# pqar-wirebonded-rev1.net
KiCad netlist of a schematic drawn in EAGLE
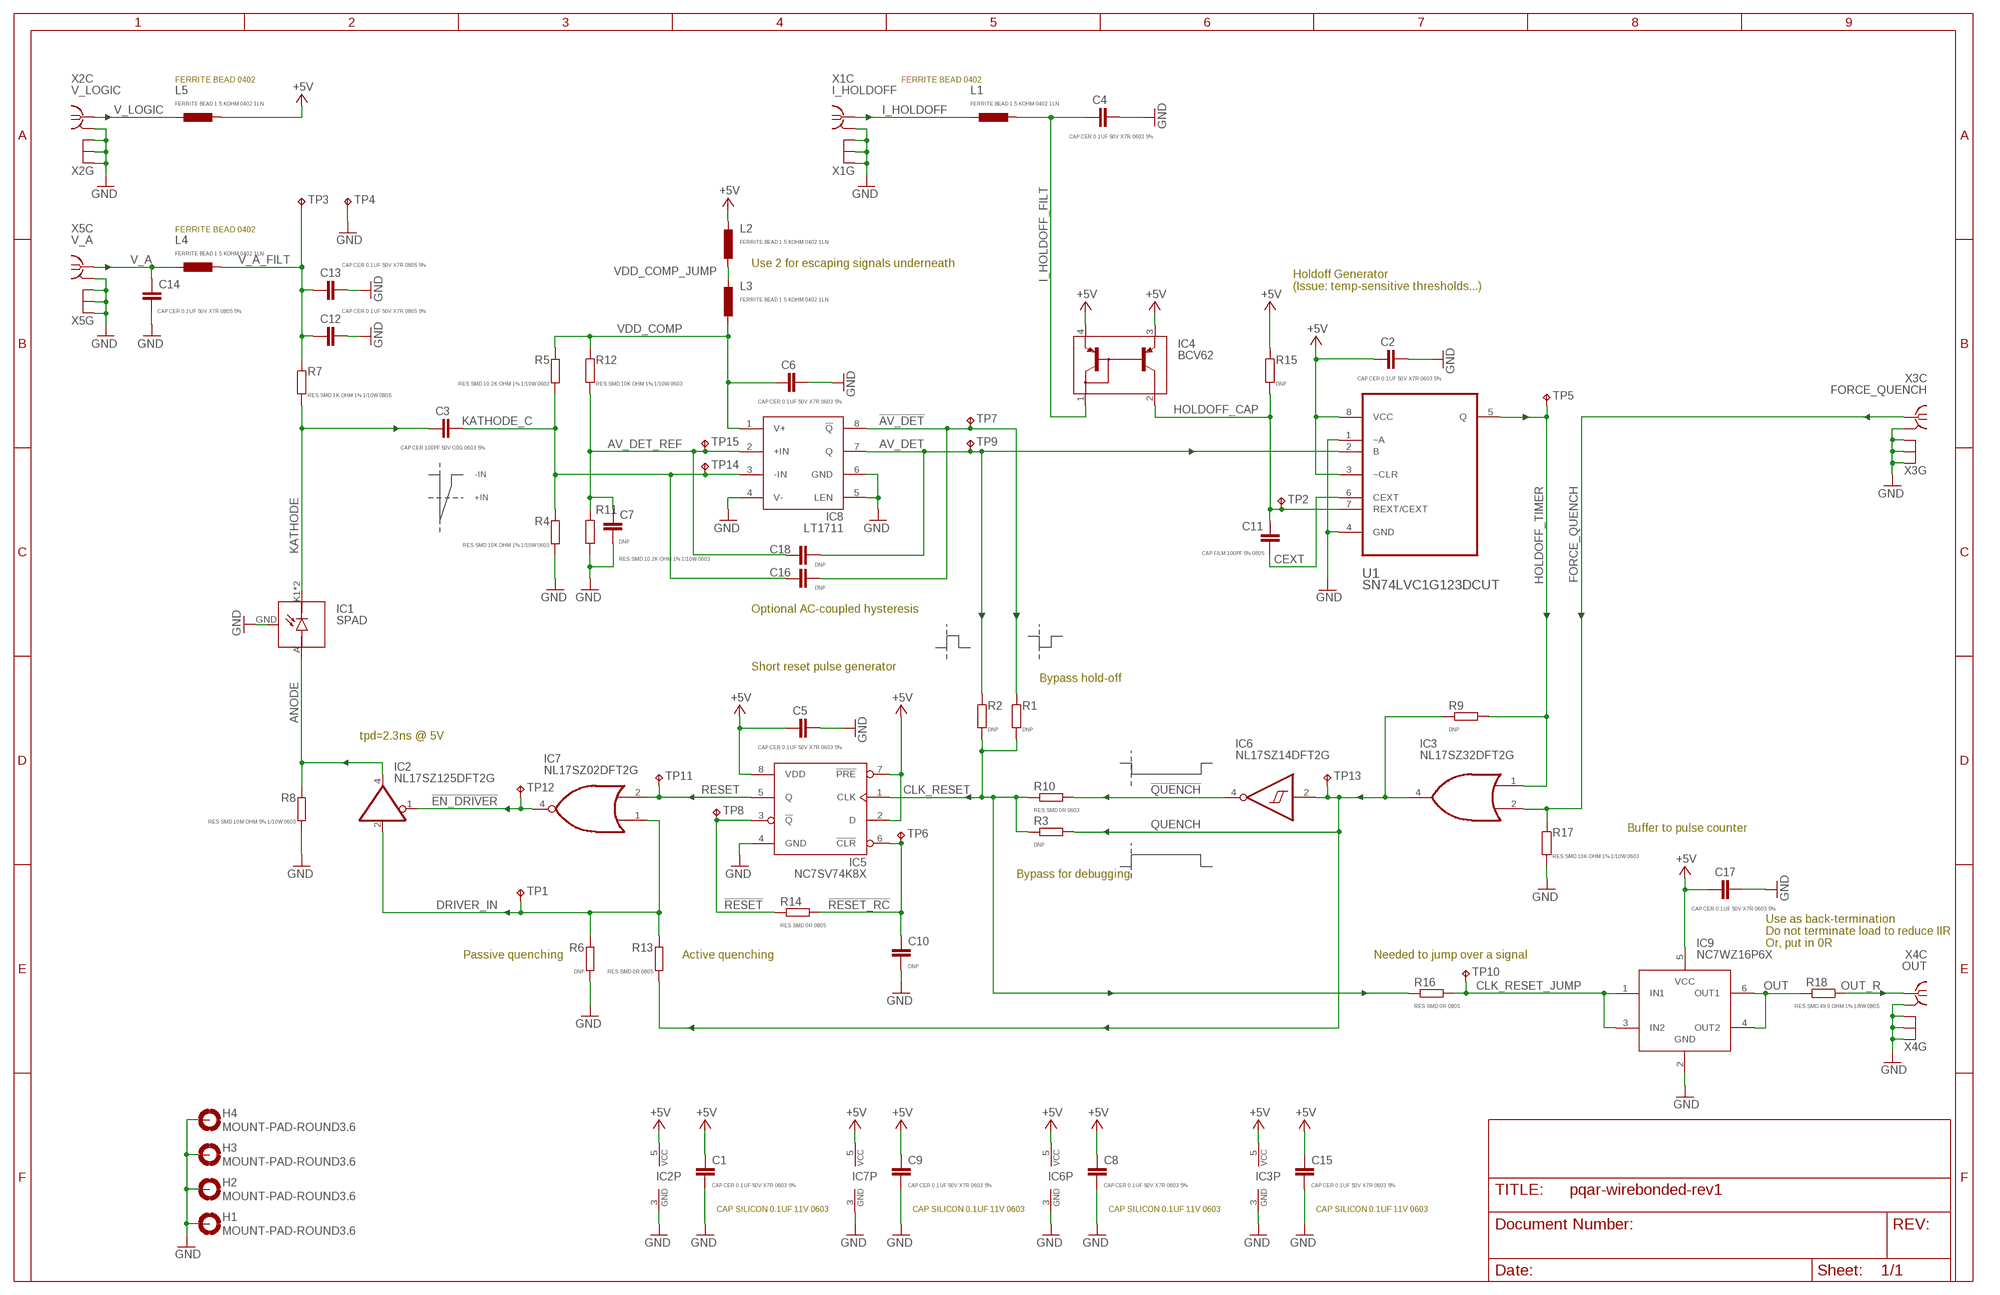
[diagram p0: schematic, sheet 1]

(export (version "E")
  (design (tool "Eeschema 10.0.6"))
  (components
    (comp (ref "C1")
      (value "CAP CER 0.1UF 50V X7R 0603 5%")
      (footprint "eagle-import:C0603")
      (libsource (lib "eagle-import") (part "C-EUC0603"))
    )
    (comp (ref "C2")
      (value "CAP CER 0.1UF 50V X7R 0603 5%")
      (footprint "eagle-import:C0603")
      (libsource (lib "eagle-import") (part "C-EUC0603"))
    )
    (comp (ref "C3")
      (value "CAP CER 100PF 50V C0G 0603 5%")
      (footprint "eagle-import:C0603")
      (libsource (lib "eagle-import") (part "C-EUC0603"))
    )
    (comp (ref "C4")
      (value "CAP CER 0.1UF 50V X7R 0603 5%")
      (footprint "eagle-import:C0603")
      (libsource (lib "eagle-import") (part "C-EUC0603"))
    )
    (comp (ref "C5")
      (value "CAP CER 0.1UF 50V X7R 0603 5%")
      (footprint "eagle-import:C0603")
      (libsource (lib "eagle-import") (part "C-EUC0603"))
    )
    (comp (ref "C6")
      (value "CAP CER 0.1UF 50V X7R 0603 5%")
      (footprint "eagle-import:C0603")
      (libsource (lib "eagle-import") (part "C-EUC0603"))
    )
    (comp (ref "C7")
      (value "DNP")
      (footprint "eagle-import:C0603")
      (libsource (lib "eagle-import") (part "C-EUC0603"))
    )
    (comp (ref "C8")
      (value "CAP CER 0.1UF 50V X7R 0603 5%")
      (footprint "eagle-import:C0603")
      (libsource (lib "eagle-import") (part "C-EUC0603"))
    )
    (comp (ref "C9")
      (value "CAP CER 0.1UF 50V X7R 0603 5%")
      (footprint "eagle-import:C0603")
      (libsource (lib "eagle-import") (part "C-EUC0603"))
    )
    (comp (ref "C10")
      (value "DNP")
      (footprint "eagle-import:C0805")
      (libsource (lib "eagle-import") (part "C-EUC0805"))
    )
    (comp (ref "C11")
      (value "CAP FILM 100PF 5% 0805")
      (footprint "eagle-import:C0805")
      (libsource (lib "eagle-import") (part "C-EUC0805"))
    )
    (comp (ref "C12")
      (value "CAP CER 0.1UF 50V X7R 0805 5%")
      (footprint "eagle-import:C0805")
      (libsource (lib "eagle-import") (part "C-EUC0805"))
    )
    (comp (ref "C13")
      (value "CAP CER 0.1UF 50V X7R 0805 5%")
      (footprint "eagle-import:C0805")
      (libsource (lib "eagle-import") (part "C-EUC0805"))
    )
    (comp (ref "C14")
      (value "CAP CER 0.1UF 50V X7R 0805 5%")
      (footprint "eagle-import:C0805")
      (libsource (lib "eagle-import") (part "C-EUC0805"))
    )
    (comp (ref "C15")
      (value "CAP CER 0.1UF 50V X7R 0603 5%")
      (footprint "eagle-import:C0603")
      (libsource (lib "eagle-import") (part "C-EUC0603"))
    )
    (comp (ref "C16")
      (value "DNP")
      (footprint "eagle-import:C0805")
      (libsource (lib "eagle-import") (part "C-EUC0805"))
    )
    (comp (ref "C17")
      (value "CAP CER 0.1UF 50V X7R 0603 5%")
      (footprint "eagle-import:C0603")
      (libsource (lib "eagle-import") (part "C-EUC0603"))
    )
    (comp (ref "C18")
      (value "DNP")
      (footprint "eagle-import:C0805")
      (libsource (lib "eagle-import") (part "C-EUC0805"))
    )
    (comp (ref "H1")
      (value "MOUNT-PAD-ROUND3.6")
      (footprint "eagle-import:3,6-PAD")
      (libsource (lib "eagle-import") (part "MOUNT-PAD-ROUND3.6"))
    )
    (comp (ref "H2")
      (value "MOUNT-PAD-ROUND3.6")
      (footprint "eagle-import:3,6-PAD")
      (libsource (lib "eagle-import") (part "MOUNT-PAD-ROUND3.6"))
    )
    (comp (ref "H3")
      (value "MOUNT-PAD-ROUND3.6")
      (footprint "eagle-import:3,6-PAD")
      (libsource (lib "eagle-import") (part "MOUNT-PAD-ROUND3.6"))
    )
    (comp (ref "H4")
      (value "MOUNT-PAD-ROUND3.6")
      (footprint "eagle-import:3,6-PAD")
      (libsource (lib "eagle-import") (part "MOUNT-PAD-ROUND3.6"))
    )
    (comp (ref "IC1")
      (value "SPAD")
      (footprint "eagle-import:SPAD-WIREBOND-GENERIC-CRYO")
      (libsource (lib "eagle-import") (part "SPAD-GENERIC"))
    )
    (comp (ref "IC2")
      (value "NL17SZ125DFT2G")
      (footprint "eagle-import:SC70-5")
      (libsource (lib "eagle-import") (part "741G125DCKAHC"))
    )
    (comp (ref "IC3")
      (value "NL17SZ32DFT2G")
      (footprint "eagle-import:SC70-5")
      (libsource (lib "eagle-import") (part "741G32DCKAUC"))
    )
    (comp (ref "IC4")
      (value "BCV62")
      (footprint "eagle-import:SOT143B")
      (libsource (lib "eagle-import") (part "BCV62"))
    )
    (comp (ref "IC5")
      (value "NC7SV74K8X")
      (footprint "eagle-import:US8_3.1MM_JDEC_MO-187")
      (libsource (lib "eagle-import") (part "NC7SV74K8X"))
    )
    (comp (ref "IC6")
      (value "NL17SZ14DFT2G")
      (footprint "eagle-import:SC70-5")
      (libsource (lib "eagle-import") (part "741G14DCKAHC"))
    )
    (comp (ref "IC7")
      (value "NL17SZ02DFT2G")
      (footprint "eagle-import:SC70-5")
      (libsource (lib "eagle-import") (part "741G02DCKLVC"))
    )
    (comp (ref "IC8")
      (value "LT1711")
      (footprint "eagle-import:MSOP8")
      (libsource (lib "eagle-import") (part "LTC1711"))
    )
    (comp (ref "IC9")
      (value "NC7WZ16P6X")
      (footprint "eagle-import:SC70-6L")
      (libsource (lib "eagle-import") (part "NC7WZ16P6X"))
    )
    (comp (ref "L1")
      (value "FERRITE BEAD 1.5 KOHM 0402 1LN")
      (footprint "eagle-import:R0402")
      (libsource (lib "eagle-import") (part "INDUCTOR0402"))
    )
    (comp (ref "L2")
      (value "FERRITE BEAD 1.5 KOHM 0402 1LN")
      (footprint "eagle-import:R0402")
      (libsource (lib "eagle-import") (part "INDUCTOR0402"))
    )
    (comp (ref "L3")
      (value "FERRITE BEAD 1.5 KOHM 0402 1LN")
      (footprint "eagle-import:R0402")
      (libsource (lib "eagle-import") (part "INDUCTOR0402"))
    )
    (comp (ref "L4")
      (value "FERRITE BEAD 1.5 KOHM 0402 1LN")
      (footprint "eagle-import:R0402")
      (libsource (lib "eagle-import") (part "INDUCTOR0402"))
    )
    (comp (ref "L5")
      (value "FERRITE BEAD 1.5 KOHM 0402 1LN")
      (footprint "eagle-import:R0402")
      (libsource (lib "eagle-import") (part "INDUCTOR0402"))
    )
    (comp (ref "R1")
      (value "DNP")
      (footprint "eagle-import:R0805")
      (libsource (lib "eagle-import") (part "rcl-modified-footprints_R-EU_R0805"))
    )
    (comp (ref "R2")
      (value "DNP")
      (footprint "eagle-import:R0805")
      (libsource (lib "eagle-import") (part "rcl-modified-footprints_R-EU_R0805"))
    )
    (comp (ref "R3")
      (value "DNP")
      (footprint "eagle-import:R0603")
      (libsource (lib "eagle-import") (part "rcl-modified-footprints_R-EU_R0603"))
    )
    (comp (ref "R4")
      (value "RES SMD 10K OHM 1% 1/10W 0603")
      (footprint "eagle-import:R0603")
      (libsource (lib "eagle-import") (part "rcl-modified-footprints_R-EU_R0603"))
    )
    (comp (ref "R5")
      (value "RES SMD 10.2K OHM 1% 1/10W 0603")
      (footprint "eagle-import:R0603")
      (libsource (lib "eagle-import") (part "rcl-modified-footprints_R-EU_R0603"))
    )
    (comp (ref "R6")
      (value "DNP")
      (footprint "eagle-import:R0805")
      (libsource (lib "eagle-import") (part "rcl-modified-footprints_R-EU_R0805"))
    )
    (comp (ref "R7")
      (value "RES SMD 1K OHM 1% 1/10W 0805")
      (footprint "eagle-import:R0805")
      (libsource (lib "eagle-import") (part "rcl-modified-footprints_R-EU_R0805"))
    )
    (comp (ref "R8")
      (value "RES SMD 10M OHM 5% 1/10W 0603")
      (footprint "eagle-import:R0603")
      (libsource (lib "eagle-import") (part "rcl-modified-footprints_R-EU_R0603"))
    )
    (comp (ref "R9")
      (value "DNP")
      (footprint "eagle-import:R0603")
      (libsource (lib "eagle-import") (part "rcl-modified-footprints_R-EU_R0603"))
    )
    (comp (ref "R10")
      (value "RES SMD 0R 0603")
      (footprint "eagle-import:R0603")
      (libsource (lib "eagle-import") (part "rcl-modified-footprints_R-EU_R0603"))
    )
    (comp (ref "R11")
      (value "RES SMD 10.2K OHM 1% 1/10W 0603")
      (footprint "eagle-import:R0603")
      (libsource (lib "eagle-import") (part "rcl-modified-footprints_R-EU_R0603"))
    )
    (comp (ref "R12")
      (value "RES SMD 10K OHM 1% 1/10W 0603")
      (footprint "eagle-import:R0603")
      (libsource (lib "eagle-import") (part "rcl-modified-footprints_R-EU_R0603"))
    )
    (comp (ref "R13")
      (value "RES SMD 0R 0805")
      (footprint "eagle-import:R0805")
      (libsource (lib "eagle-import") (part "rcl-modified-footprints_R-EU_R0805"))
    )
    (comp (ref "R14")
      (value "RES SMD 0R 0805")
      (footprint "eagle-import:R0805")
      (libsource (lib "eagle-import") (part "rcl-modified-footprints_R-EU_R0805"))
    )
    (comp (ref "R15")
      (value "DNP")
      (footprint "eagle-import:R0805")
      (libsource (lib "eagle-import") (part "rcl-modified-footprints_R-EU_R0805"))
    )
    (comp (ref "R16")
      (value "RES SMD 0R 0805")
      (footprint "eagle-import:R0805")
      (libsource (lib "eagle-import") (part "rcl-modified-footprints_R-EU_R0805"))
    )
    (comp (ref "R17")
      (value "RES SMD 10K OHM 1% 1/10W 0603")
      (footprint "eagle-import:R0603")
      (libsource (lib "eagle-import") (part "rcl-modified-footprints_R-EU_R0603"))
    )
    (comp (ref "R18")
      (value "RES SMD 49.9 OHM 1% 1/8W 0805")
      (footprint "eagle-import:R0805")
      (libsource (lib "eagle-import") (part "R-EU_R0805"))
    )
    (comp (ref "TP1")
      (value "AV_DET")
      (footprint "eagle-import:TP10R")
      (libsource (lib "eagle-import") (part "TPTP10R"))
    )
    (comp (ref "TP2")
      (value "AV_DET")
      (footprint "eagle-import:TP10R")
      (libsource (lib "eagle-import") (part "TPTP10R"))
    )
    (comp (ref "TP3")
      (value "AV_DET")
      (footprint "eagle-import:TP10R")
      (libsource (lib "eagle-import") (part "TPTP10R"))
    )
    (comp (ref "TP4")
      (value "AV_DET")
      (footprint "eagle-import:TP10R")
      (libsource (lib "eagle-import") (part "TPTP10R"))
    )
    (comp (ref "TP5")
      (value "AV_DET")
      (footprint "eagle-import:TP10R")
      (libsource (lib "eagle-import") (part "TPTP10R"))
    )
    (comp (ref "TP6")
      (value "AV_DET")
      (footprint "eagle-import:TP10R")
      (libsource (lib "eagle-import") (part "TPTP10R"))
    )
    (comp (ref "TP7")
      (value "AV_DET")
      (footprint "eagle-import:TP10R")
      (libsource (lib "eagle-import") (part "TPTP10R"))
    )
    (comp (ref "TP8")
      (value "AV_DET")
      (footprint "eagle-import:TP10R")
      (libsource (lib "eagle-import") (part "TPTP10R"))
    )
    (comp (ref "TP9")
      (value "AV_DET")
      (footprint "eagle-import:TP10R")
      (libsource (lib "eagle-import") (part "TPTP10R"))
    )
    (comp (ref "TP10")
      (value "AV_DET")
      (footprint "eagle-import:TP10R")
      (libsource (lib "eagle-import") (part "TPTP10R"))
    )
    (comp (ref "TP11")
      (value "AV_DET")
      (footprint "eagle-import:TP10R")
      (libsource (lib "eagle-import") (part "TPTP10R"))
    )
    (comp (ref "TP12")
      (value "AV_DET")
      (footprint "eagle-import:TP10R")
      (libsource (lib "eagle-import") (part "TPTP10R"))
    )
    (comp (ref "TP13")
      (value "AV_DET")
      (footprint "eagle-import:TP10R")
      (libsource (lib "eagle-import") (part "TPTP10R"))
    )
    (comp (ref "TP14")
      (value "AV_DET")
      (footprint "eagle-import:TP10R")
      (libsource (lib "eagle-import") (part "TPTP10R"))
    )
    (comp (ref "TP15")
      (value "AV_DET")
      (footprint "eagle-import:TP10R")
      (libsource (lib "eagle-import") (part "TPTP10R"))
    )
    (comp (ref "U1")
      (value "SN74LVC1G123DCUT")
      (footprint "eagle-import:SOP50P310X90-8N")
      (libsource (lib "eagle-import") (part "SN74LVC1G123DCUT"))
    )
    (comp (ref "X1")
      (value "I_HOLDOFF")
      (footprint "eagle-import:MMCX-SMT-BIGPADS")
      (libsource (lib "eagle-import") (part "MMCXBIGPAD"))
    )
    (comp (ref "X2")
      (value "V_LOGIC")
      (footprint "eagle-import:MMCX-SMT-BIGPADS")
      (libsource (lib "eagle-import") (part "MMCXBIGPAD"))
    )
    (comp (ref "X3")
      (value "FORCE_QUENCH")
      (footprint "eagle-import:MMCX-SMT-BIGPADS")
      (libsource (lib "eagle-import") (part "MMCXBIGPAD"))
    )
    (comp (ref "X4")
      (value "OUT")
      (footprint "eagle-import:MMCX-SMT-BIGPADS")
      (libsource (lib "eagle-import") (part "MMCXBIGPAD"))
    )
    (comp (ref "X5")
      (value "V_A")
      (footprint "eagle-import:MMCX-SMT-BIGPADS")
      (libsource (lib "eagle-import") (part "MMCXBIGPAD"))
    )
  )
  (nets
    (net (code "1") (name "+5V") (class "Default")
      (node (ref "C1") (pin "1") (pinfunction "1_1") (pintype "passive"))
      (node (ref "C15") (pin "1") (pinfunction "1_1") (pintype "passive"))
      (node (ref "C17") (pin "1") (pinfunction "1_1") (pintype "passive"))
      (node (ref "C2") (pin "1") (pinfunction "1_1") (pintype "passive"))
      (node (ref "C5") (pin "1") (pinfunction "1_1") (pintype "passive"))
      (node (ref "C8") (pin "1") (pinfunction "1_1") (pintype "passive"))
      (node (ref "C9") (pin "1") (pinfunction "1_1") (pintype "passive"))
      (node (ref "IC2") (pin "5") (pinfunction "VCC_5") (pintype "power_in"))
      (node (ref "IC3") (pin "5") (pinfunction "VCC_5") (pintype "power_in"))
      (node (ref "IC4") (pin "3") (pinfunction "E_OUT_3") (pintype "passive"))
      (node (ref "IC4") (pin "4") (pinfunction "E_IN_4") (pintype "passive"))
      (node (ref "IC5") (pin "2") (pinfunction "D_2") (pintype "bidirectional"))
      (node (ref "IC5") (pin "7") (pinfunction "~{PRE}_7") (pintype "bidirectional"))
      (node (ref "IC5") (pin "8") (pinfunction "VDD_8") (pintype "bidirectional"))
      (node (ref "IC6") (pin "5") (pinfunction "VCC_5") (pintype "power_in"))
      (node (ref "IC7") (pin "5") (pinfunction "VCC_5") (pintype "power_in"))
      (node (ref "IC9") (pin "5") (pinfunction "VCC_5") (pintype "bidirectional"))
      (node (ref "L2") (pin "1") (pinfunction "P$1_1") (pintype "bidirectional"))
      (node (ref "L5") (pin "2") (pinfunction "P$2_2") (pintype "bidirectional"))
      (node (ref "R15") (pin "1") (pinfunction "1_1") (pintype "passive"))
      (node (ref "U1") (pin "3") (pinfunction "~{CLR}_3") (pintype "input"))
      (node (ref "U1") (pin "8") (pinfunction "VCC_8") (pintype "power_in"))
    )
    (net (code "2") (name "/ANODE") (class "Default")
      (node (ref "IC1") (pin "A") (pinfunction "SPAD_ANODE_A") (pintype "bidirectional"))
      (node (ref "IC2") (pin "4") (pinfunction "O_4") (pintype "tri_state"))
      (node (ref "R8") (pin "1") (pinfunction "1_1") (pintype "passive"))
    )
    (net (code "3") (name "/AV_DET") (class "Default")
      (node (ref "C18") (pin "2") (pinfunction "2_2") (pintype "passive"))
      (node (ref "IC8") (pin "7") (pinfunction "Q_7") (pintype "bidirectional"))
      (node (ref "R2") (pin "1") (pinfunction "1_1") (pintype "passive"))
      (node (ref "TP9") (pin "TP") (pinfunction "TP_TP") (pintype "input"))
      (node (ref "U1") (pin "2") (pinfunction "B_2") (pintype "input"))
    )
    (net (code "4") (name "/AV_DET_REF") (class "Default")
      (node (ref "C18") (pin "1") (pinfunction "1_1") (pintype "passive"))
      (node (ref "C7") (pin "1") (pinfunction "1_1") (pintype "passive"))
      (node (ref "IC8") (pin "2") (pinfunction "+IN_2") (pintype "bidirectional"))
      (node (ref "R11") (pin "1") (pinfunction "1_1") (pintype "passive"))
      (node (ref "R12") (pin "2") (pinfunction "2_2") (pintype "passive"))
      (node (ref "TP15") (pin "TP") (pinfunction "TP_TP") (pintype "input"))
    )
    (net (code "5") (name "/CEXT") (class "Default")
      (node (ref "C11") (pin "2") (pinfunction "2_2") (pintype "passive"))
      (node (ref "U1") (pin "6") (pinfunction "CEXT_6") (pintype "passive"))
    )
    (net (code "6") (name "/CLK_RESET") (class "Default")
      (node (ref "IC5") (pin "1") (pinfunction "CLK_1") (pintype "bidirectional"))
      (node (ref "R1") (pin "2") (pinfunction "2_2") (pintype "passive"))
      (node (ref "R10") (pin "1") (pinfunction "1_1") (pintype "passive"))
      (node (ref "R16") (pin "1") (pinfunction "1_1") (pintype "passive"))
      (node (ref "R2") (pin "2") (pinfunction "2_2") (pintype "passive"))
      (node (ref "R3") (pin "1") (pinfunction "1_1") (pintype "passive"))
    )
    (net (code "7") (name "/CLK_RESET_JUMP") (class "Default")
      (node (ref "IC9") (pin "1") (pinfunction "IN1_1") (pintype "bidirectional"))
      (node (ref "IC9") (pin "3") (pinfunction "IN2_3") (pintype "bidirectional"))
      (node (ref "R16") (pin "2") (pinfunction "2_2") (pintype "passive"))
      (node (ref "TP10") (pin "TP") (pinfunction "TP_TP") (pintype "input"))
    )
    (net (code "8") (name "/DRIVER_IN") (class "Default")
      (node (ref "IC2") (pin "2") (pinfunction "I_2") (pintype "input"))
      (node (ref "IC7") (pin "1") (pinfunction "I0_1") (pintype "input"))
      (node (ref "R13") (pin "1") (pinfunction "1_1") (pintype "passive"))
      (node (ref "R6") (pin "1") (pinfunction "1_1") (pintype "passive"))
      (node (ref "TP1") (pin "TP") (pinfunction "TP_TP") (pintype "input"))
    )
    (net (code "9") (name "/FORCE_QUENCH") (class "Default")
      (node (ref "IC3") (pin "2") (pinfunction "I1_2") (pintype "input"))
      (node (ref "R17") (pin "1") (pinfunction "1_1") (pintype "passive"))
      (node (ref "X3") (pin "S") (pinfunction "1_S") (pintype "passive"))
    )
    (net (code "10") (name "/HOLDOFF_CAP") (class "Default")
      (node (ref "C11") (pin "1") (pinfunction "1_1") (pintype "passive"))
      (node (ref "IC4") (pin "2") (pinfunction "C_OUT_2") (pintype "passive"))
      (node (ref "R15") (pin "2") (pinfunction "2_2") (pintype "passive"))
      (node (ref "TP2") (pin "TP") (pinfunction "TP_TP") (pintype "input"))
      (node (ref "U1") (pin "7") (pinfunction "REXT/CEXT_7") (pintype "passive"))
    )
    (net (code "11") (name "/HOLDOFF_TIMER") (class "Default")
      (node (ref "IC3") (pin "1") (pinfunction "I0_1") (pintype "input"))
      (node (ref "R9") (pin "2") (pinfunction "2_2") (pintype "passive"))
      (node (ref "TP5") (pin "TP") (pinfunction "TP_TP") (pintype "input"))
      (node (ref "U1") (pin "5") (pinfunction "Q_5") (pintype "output"))
    )
    (net (code "12") (name "/I_HOLDOFF") (class "Default")
      (node (ref "L1") (pin "1") (pinfunction "P$1_1") (pintype "bidirectional"))
      (node (ref "X1") (pin "S") (pinfunction "1_S") (pintype "passive"))
    )
    (net (code "13") (name "/I_HOLDOFF_FILT") (class "Default")
      (node (ref "C4") (pin "1") (pinfunction "1_1") (pintype "passive"))
      (node (ref "IC4") (pin "1") (pinfunction "BC_IN_1") (pintype "passive"))
      (node (ref "L1") (pin "2") (pinfunction "P$2_2") (pintype "bidirectional"))
    )
    (net (code "14") (name "/KATHODE") (class "Default")
      (node (ref "C3") (pin "1") (pinfunction "1_1") (pintype "passive"))
      (node (ref "IC1") (pin "K1") (pinfunction "SPAD_CATHODE_K1") (pintype "bidirectional"))
      (node (ref "IC1") (pin "K2") (pinfunction "SPAD_CATHODE_K2") (pintype "bidirectional"))
      (node (ref "R7") (pin "2") (pinfunction "2_2") (pintype "passive"))
    )
    (net (code "15") (name "/KATHODE_C") (class "Default")
      (node (ref "C16") (pin "1") (pinfunction "1_1") (pintype "passive"))
      (node (ref "C3") (pin "2") (pinfunction "2_2") (pintype "passive"))
      (node (ref "IC8") (pin "3") (pinfunction "-IN_3") (pintype "bidirectional"))
      (node (ref "R4") (pin "1") (pinfunction "1_1") (pintype "passive"))
      (node (ref "R5") (pin "2") (pinfunction "2_2") (pintype "passive"))
      (node (ref "TP14") (pin "TP") (pinfunction "TP_TP") (pintype "input"))
    )
    (net (code "16") (name "/OUT") (class "Default")
      (node (ref "IC9") (pin "4") (pinfunction "OUT2_4") (pintype "bidirectional"))
      (node (ref "IC9") (pin "6") (pinfunction "OUT1_6") (pintype "bidirectional"))
      (node (ref "R18") (pin "2") (pinfunction "2_2") (pintype "passive"))
    )
    (net (code "17") (name "/OUT_R") (class "Default")
      (node (ref "R18") (pin "1") (pinfunction "1_1") (pintype "passive"))
      (node (ref "X4") (pin "S") (pinfunction "1_S") (pintype "passive"))
    )
    (net (code "18") (name "/QUENCH") (class "Default")
      (node (ref "IC3") (pin "4") (pinfunction "O_4") (pintype "output"))
      (node (ref "IC6") (pin "2") (pinfunction "I_2") (pintype "input"))
      (node (ref "R13") (pin "2") (pinfunction "2_2") (pintype "passive"))
      (node (ref "R3") (pin "2") (pinfunction "2_2") (pintype "passive"))
      (node (ref "R9") (pin "1") (pinfunction "1_1") (pintype "passive"))
      (node (ref "TP13") (pin "TP") (pinfunction "TP_TP") (pintype "input"))
    )
    (net (code "19") (name "/RESET") (class "Default")
      (node (ref "IC5") (pin "5") (pinfunction "Q_5") (pintype "bidirectional"))
      (node (ref "IC7") (pin "2") (pinfunction "I1_2") (pintype "input"))
      (node (ref "TP11") (pin "TP") (pinfunction "TP_TP") (pintype "input"))
    )
    (net (code "20") (name "/VDD_COMP") (class "Default")
      (node (ref "C6") (pin "1") (pinfunction "1_1") (pintype "passive"))
      (node (ref "IC8") (pin "1") (pinfunction "V+_1") (pintype "bidirectional"))
      (node (ref "L3") (pin "2") (pinfunction "P$2_2") (pintype "bidirectional"))
      (node (ref "R12") (pin "1") (pinfunction "1_1") (pintype "passive"))
      (node (ref "R5") (pin "1") (pinfunction "1_1") (pintype "passive"))
    )
    (net (code "21") (name "/VDD_COMP_JUMP") (class "Default")
      (node (ref "L2") (pin "2") (pinfunction "P$2_2") (pintype "bidirectional"))
      (node (ref "L3") (pin "1") (pinfunction "P$1_1") (pintype "bidirectional"))
    )
    (net (code "22") (name "/V_A") (class "Default")
      (node (ref "C14") (pin "1") (pinfunction "1_1") (pintype "passive"))
      (node (ref "L4") (pin "1") (pinfunction "P$1_1") (pintype "bidirectional"))
      (node (ref "X5") (pin "S") (pinfunction "1_S") (pintype "passive"))
    )
    (net (code "23") (name "/V_A_FILT") (class "Default")
      (node (ref "C12") (pin "1") (pinfunction "1_1") (pintype "passive"))
      (node (ref "C13") (pin "1") (pinfunction "1_1") (pintype "passive"))
      (node (ref "L4") (pin "2") (pinfunction "P$2_2") (pintype "bidirectional"))
      (node (ref "R7") (pin "1") (pinfunction "1_1") (pintype "passive"))
      (node (ref "TP3") (pin "TP") (pinfunction "TP_TP") (pintype "input"))
    )
    (net (code "24") (name "/V_LOGIC") (class "Default")
      (node (ref "L5") (pin "1") (pinfunction "P$1_1") (pintype "bidirectional"))
      (node (ref "X2") (pin "S") (pinfunction "1_S") (pintype "passive"))
    )
    (net (code "25") (name "/~{AV_DET}") (class "Default")
      (node (ref "C16") (pin "2") (pinfunction "2_2") (pintype "passive"))
      (node (ref "IC8") (pin "8") (pinfunction "~{Q}_8") (pintype "bidirectional"))
      (node (ref "R1") (pin "1") (pinfunction "1_1") (pintype "passive"))
      (node (ref "TP7") (pin "TP") (pinfunction "TP_TP") (pintype "input"))
    )
    (net (code "26") (name "/~{EN_DRIVER}") (class "Default")
      (node (ref "IC2") (pin "1") (pinfunction "OE_1") (pintype "input"))
      (node (ref "IC7") (pin "4") (pinfunction "O_4") (pintype "output"))
      (node (ref "TP12") (pin "TP") (pinfunction "TP_TP") (pintype "input"))
    )
    (net (code "27") (name "/~{QUENCH}") (class "Default")
      (node (ref "IC6") (pin "4") (pinfunction "O_4") (pintype "output"))
      (node (ref "R10") (pin "2") (pinfunction "2_2") (pintype "passive"))
    )
    (net (code "28") (name "/~{RESET_RC}") (class "Default")
      (node (ref "C10") (pin "1") (pinfunction "1_1") (pintype "passive"))
      (node (ref "IC5") (pin "6") (pinfunction "~{CLR}_6") (pintype "bidirectional"))
      (node (ref "R14") (pin "2") (pinfunction "2_2") (pintype "passive"))
      (node (ref "TP6") (pin "TP") (pinfunction "TP_TP") (pintype "input"))
    )
    (net (code "29") (name "/~{RESET}") (class "Default")
      (node (ref "IC5") (pin "3") (pinfunction "~{Q}_3") (pintype "bidirectional"))
      (node (ref "R14") (pin "1") (pinfunction "1_1") (pintype "passive"))
      (node (ref "TP8") (pin "TP") (pinfunction "TP_TP") (pintype "input"))
    )
    (net (code "30") (name "GND") (class "Default")
      (node (ref "C1") (pin "2") (pinfunction "2_2") (pintype "passive"))
      (node (ref "C10") (pin "2") (pinfunction "2_2") (pintype "passive"))
      (node (ref "C12") (pin "2") (pinfunction "2_2") (pintype "passive"))
      (node (ref "C13") (pin "2") (pinfunction "2_2") (pintype "passive"))
      (node (ref "C14") (pin "2") (pinfunction "2_2") (pintype "passive"))
      (node (ref "C15") (pin "2") (pinfunction "2_2") (pintype "passive"))
      (node (ref "C17") (pin "2") (pinfunction "2_2") (pintype "passive"))
      (node (ref "C2") (pin "2") (pinfunction "2_2") (pintype "passive"))
      (node (ref "C4") (pin "2") (pinfunction "2_2") (pintype "passive"))
      (node (ref "C5") (pin "2") (pinfunction "2_2") (pintype "passive"))
      (node (ref "C6") (pin "2") (pinfunction "2_2") (pintype "passive"))
      (node (ref "C7") (pin "2") (pinfunction "2_2") (pintype "passive"))
      (node (ref "C8") (pin "2") (pinfunction "2_2") (pintype "passive"))
      (node (ref "C9") (pin "2") (pinfunction "2_2") (pintype "passive"))
      (node (ref "H1") (pin "B3,6") (pinfunction "MOUNT_B3,6") (pintype "passive"))
      (node (ref "H2") (pin "B3,6") (pinfunction "MOUNT_B3,6") (pintype "passive"))
      (node (ref "H3") (pin "B3,6") (pinfunction "MOUNT_B3,6") (pintype "passive"))
      (node (ref "H4") (pin "B3,6") (pinfunction "MOUNT_B3,6") (pintype "passive"))
      (node (ref "IC1") (pin "GND") (pinfunction "GND_GND") (pintype "bidirectional"))
      (node (ref "IC2") (pin "3") (pinfunction "GND_3") (pintype "power_in"))
      (node (ref "IC3") (pin "3") (pinfunction "GND_3") (pintype "power_in"))
      (node (ref "IC5") (pin "4") (pinfunction "GND_4") (pintype "bidirectional"))
      (node (ref "IC6") (pin "3") (pinfunction "GND_3") (pintype "power_in"))
      (node (ref "IC7") (pin "3") (pinfunction "GND_3") (pintype "power_in"))
      (node (ref "IC8") (pin "4") (pinfunction "V-_4") (pintype "bidirectional"))
      (node (ref "IC8") (pin "5") (pinfunction "LEN_5") (pintype "bidirectional"))
      (node (ref "IC8") (pin "6") (pinfunction "GND_6") (pintype "bidirectional"))
      (node (ref "IC9") (pin "2") (pinfunction "GND_2") (pintype "bidirectional"))
      (node (ref "R11") (pin "2") (pinfunction "2_2") (pintype "passive"))
      (node (ref "R17") (pin "2") (pinfunction "2_2") (pintype "passive"))
      (node (ref "R4") (pin "2") (pinfunction "2_2") (pintype "passive"))
      (node (ref "R6") (pin "2") (pinfunction "2_2") (pintype "passive"))
      (node (ref "R8") (pin "2") (pinfunction "2_2") (pintype "passive"))
      (node (ref "TP4") (pin "TP") (pinfunction "TP_TP") (pintype "input"))
      (node (ref "U1") (pin "1") (pinfunction "~{A}_1") (pintype "input"))
      (node (ref "U1") (pin "4") (pinfunction "GND_4") (pintype "passive"))
      (node (ref "X1") (pin "G1") (pinfunction "GND_G1") (pintype "power_in"))
      (node (ref "X1") (pin "G2") (pinfunction "GND_G2") (pintype "power_in"))
      (node (ref "X1") (pin "G3") (pinfunction "GND_G3") (pintype "power_in"))
      (node (ref "X1") (pin "G4") (pinfunction "GND_G4") (pintype "power_in"))
      (node (ref "X2") (pin "G1") (pinfunction "GND_G1") (pintype "power_in"))
      (node (ref "X2") (pin "G2") (pinfunction "GND_G2") (pintype "power_in"))
      (node (ref "X2") (pin "G3") (pinfunction "GND_G3") (pintype "power_in"))
      (node (ref "X2") (pin "G4") (pinfunction "GND_G4") (pintype "power_in"))
      (node (ref "X3") (pin "G1") (pinfunction "GND_G1") (pintype "power_in"))
      (node (ref "X3") (pin "G2") (pinfunction "GND_G2") (pintype "power_in"))
      (node (ref "X3") (pin "G3") (pinfunction "GND_G3") (pintype "power_in"))
      (node (ref "X3") (pin "G4") (pinfunction "GND_G4") (pintype "power_in"))
      (node (ref "X4") (pin "G1") (pinfunction "GND_G1") (pintype "power_in"))
      (node (ref "X4") (pin "G2") (pinfunction "GND_G2") (pintype "power_in"))
      (node (ref "X4") (pin "G3") (pinfunction "GND_G3") (pintype "power_in"))
      (node (ref "X4") (pin "G4") (pinfunction "GND_G4") (pintype "power_in"))
      (node (ref "X5") (pin "G1") (pinfunction "GND_G1") (pintype "power_in"))
      (node (ref "X5") (pin "G2") (pinfunction "GND_G2") (pintype "power_in"))
      (node (ref "X5") (pin "G3") (pinfunction "GND_G3") (pintype "power_in"))
      (node (ref "X5") (pin "G4") (pinfunction "GND_G4") (pintype "power_in"))
    )
  )
)
